# CH32V317W-R0-1v0.net
KiCad netlist of a schematic drawn in Altium Designer
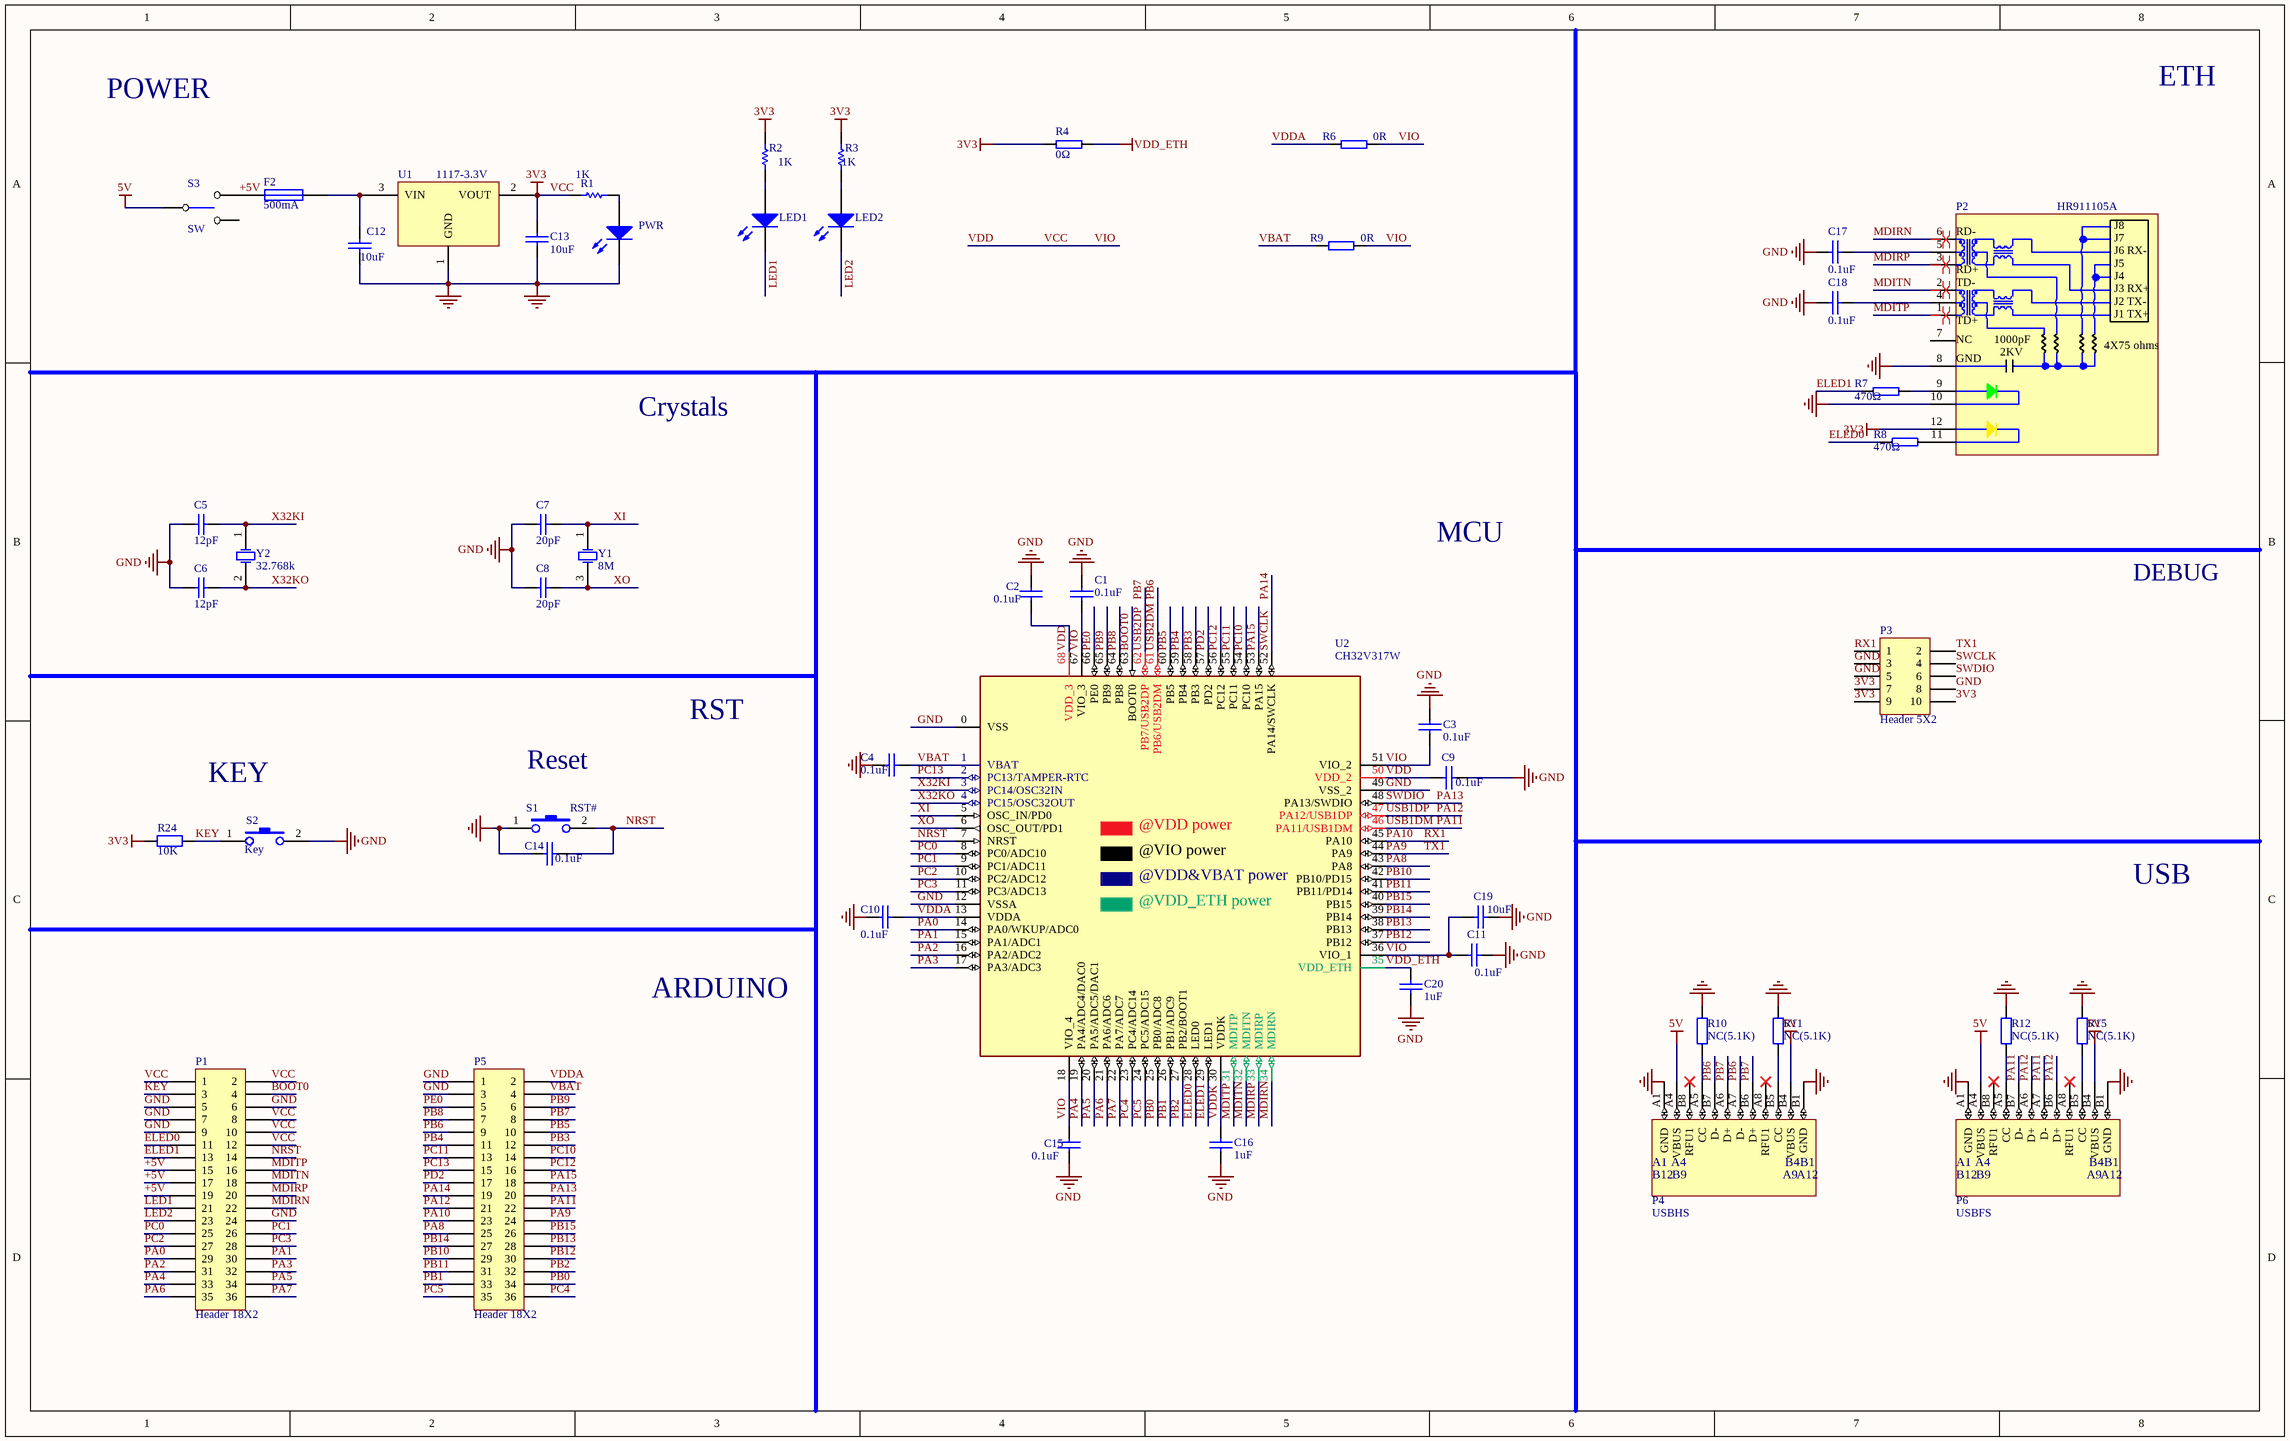
[diagram p0: CH32V317W-R0-1v0.SchDoc]

(export (version "E")
  (design (tool "Eeschema 10.0.6"))
  (components
    (comp (ref "C1")
      (value "0.1uF")
      (footprint "0603_C")
      (description "Capacitor")
      (libsource (lib "*") (part "CAP"))
    )
    (comp (ref "C2")
      (value "0.1uF")
      (footprint "0603_C")
      (description "Capacitor")
      (libsource (lib "*") (part "CAP"))
    )
    (comp (ref "C3")
      (value "0.1uF")
      (footprint "0603_C")
      (description "Capacitor")
      (libsource (lib "*") (part "CAP"))
    )
    (comp (ref "C4")
      (value "0.1uF")
      (footprint "0603_C")
      (description "Capacitor")
      (libsource (lib "*") (part "CAP"))
    )
    (comp (ref "C5")
      (value "12pF")
      (footprint "0603_C")
      (description "Capacitor")
      (libsource (lib "Miscellaneous Devices") (part "Cap"))
    )
    (comp (ref "C6")
      (value "12pF")
      (footprint "0603_C")
      (description "Capacitor")
      (libsource (lib "Miscellaneous Devices") (part "Cap"))
    )
    (comp (ref "C7")
      (value "20pF")
      (footprint "0603_C")
      (description "Capacitor")
      (libsource (lib "Miscellaneous Devices") (part "Cap"))
    )
    (comp (ref "C8")
      (value "20pF")
      (footprint "0603_C")
      (description "Capacitor")
      (libsource (lib "Miscellaneous Devices") (part "Cap"))
    )
    (comp (ref "C9")
      (value "0.1uF")
      (footprint "0603_C")
      (description "Capacitor")
      (libsource (lib "*") (part "CAP"))
    )
    (comp (ref "C10")
      (value "0.1uF")
      (footprint "0603_C")
      (description "Capacitor")
      (libsource (lib "*") (part "CAP"))
    )
    (comp (ref "C11")
      (value "0.1uF")
      (footprint "0603_C")
      (description "Capacitor")
      (libsource (lib "*") (part "CAP"))
    )
    (comp (ref "C12")
      (value "10uF")
      (footprint "0603_C")
      (description "Capacitor")
      (libsource (lib "*") (part "CAP"))
    )
    (comp (ref "C13")
      (value "10uF")
      (footprint "0603_C")
      (description "Capacitor")
      (libsource (lib "*") (part "CAP"))
    )
    (comp (ref "C14")
      (value "0.1uF")
      (footprint "0603_C")
      (description "Capacitor")
      (libsource (lib "") (part "CAP_1"))
    )
    (comp (ref "C15")
      (value "0.1uF")
      (footprint "0603_C")
      (description "Capacitor")
      (libsource (lib "*") (part "CAP"))
    )
    (comp (ref "C16")
      (value "1uF")
      (footprint "0603_C")
      (description "Capacitor")
      (libsource (lib "wch_sch_others") (part "CAP"))
    )
    (comp (ref "C17")
      (value "0.1uF")
      (footprint "0603_C")
      (description "Capacitor")
      (libsource (lib "wch_sch_others") (part "CAP"))
    )
    (comp (ref "C18")
      (value "0.1uF")
      (footprint "0603_C")
      (description "Capacitor")
      (libsource (lib "wch_sch_others") (part "CAP"))
    )
    (comp (ref "C19")
      (value "10uF")
      (footprint "0603_C")
      (description "Capacitor")
      (libsource (lib "*") (part "CAP"))
    )
    (comp (ref "C20")
      (value "1uF")
      (footprint "0603_C")
      (description "Capacitor")
      (libsource (lib "*") (part "CAP"))
    )
    (comp (ref "F2")
      (value "500mA")
      (footprint "0603")
      (description "Fuse")
      (libsource (lib "*") (part "FUSE1"))
    )
    (comp (ref "LED1")
      (value "LED1   blue")
      (footprint "0603+")
      (description "Typical INFRARED GaAs LED")
      (fields (field (name "PUBLISHER") "Altium Limited"))
      (libsource (lib "Miscellaneous Devices") (part "LED0"))
    )
    (comp (ref "LED2")
      (value "LED2  blue")
      (footprint "0603+")
      (description "Typical INFRARED GaAs LED")
      (fields (field (name "PUBLISHER") "Altium Limited"))
      (libsource (lib "Miscellaneous Devices") (part "LED0"))
    )
    (comp (ref "P1")
      (value "Header 18X2")
      (footprint "IDC36-2.54mm")
      (description "Header, 18-Pin, Dual row")
      (fields (field (name "PUBLISHER") "Altium Limited"))
      (libsource (lib "Miscellaneous Connectors") (part "Header 18X2"))
    )
    (comp (ref "P2") (value "HR911105A") (footprint "HR911105A") (libsource (lib "*") (part "HR911105A")))
    (comp (ref "P3")
      (value "Header 5X2")
      (footprint "IDC10-2.54mm")
      (description "Header, 5-Pin, Dual row")
      (fields (field (name "PUBLISHER") "Altium Limited"))
      (libsource (lib "Miscellaneous Connectors") (part "Header 5X2"))
    )
    (comp (ref "P4")
      (value "USBHS")
      (footprint "TYPE-C-Receptacle-2.0")
      (libsource (lib "*") (part "TYPE-C1"))
    )
    (comp (ref "P5")
      (value "Header 18X2")
      (footprint "IDC36-2.54mm")
      (description "Header, 18-Pin, Dual row")
      (fields (field (name "PUBLISHER") "Altium Limited"))
      (libsource (lib "Miscellaneous Connectors") (part "Header 18X2"))
    )
    (comp (ref "P6")
      (value "USBFS")
      (footprint "TYPE-C-Receptacle-2.0")
      (libsource (lib "*") (part "TYPE-C1"))
    )
    (comp (ref "PWR")
      (value "POWER  red")
      (footprint "0603+")
      (description "Typical INFRARED GaAs LED")
      (fields (field (name "PUBLISHER") "Altium Limited"))
      (libsource (lib "Miscellaneous Devices") (part "LED0"))
    )
    (comp (ref "R1")
      (value "1K")
      (footprint "0603")
      (description "Semiconductor Resistor")
      (libsource (lib "Miscellaneous Devices") (part "Res Semi"))
    )
    (comp (ref "R2")
      (value "1K")
      (footprint "0603")
      (description "Semiconductor Resistor")
      (libsource (lib "Miscellaneous Devices") (part "Res Semi"))
    )
    (comp (ref "R3")
      (value "1K")
      (footprint "0603")
      (description "Semiconductor Resistor")
      (libsource (lib "Miscellaneous Devices") (part "Res Semi"))
    )
    (comp (ref "R4") (value "0Ω") (footprint "0603") (libsource (lib "wch_sch_others") (part "RES")))
    (comp (ref "R6") (value "0R") (footprint "0603") (libsource (lib "*") (part "R")))
    (comp (ref "R7") (value "470Ω") (footprint "0603") (libsource (lib "") (part "RES_1")))
    (comp (ref "R8") (value "470Ω") (footprint "0603") (libsource (lib "") (part "RES_1")))
    (comp (ref "R9") (value "0R") (footprint "0603") (libsource (lib "*") (part "R")))
    (comp (ref "R10")
      (value "NC(5.1K)")
      (footprint "0603")
      (description "Resistor")
      (libsource (lib "Miscellaneous Devices") (part "Res2"))
    )
    (comp (ref "R11")
      (value "NC(5.1K)")
      (footprint "0603")
      (description "Resistor")
      (libsource (lib "Miscellaneous Devices") (part "Res2"))
    )
    (comp (ref "R12")
      (value "NC(5.1K)")
      (footprint "0603")
      (description "Resistor")
      (libsource (lib "Miscellaneous Devices") (part "Res2"))
    )
    (comp (ref "R15")
      (value "NC(5.1K)")
      (footprint "0603")
      (description "Resistor")
      (libsource (lib "Miscellaneous Devices") (part "Res2"))
    )
    (comp (ref "R24")
      (value "10K")
      (footprint "0603")
      (description "Resistor")
      (libsource (lib "") (part "Res2_1"))
    )
    (comp (ref "S1")
      (value "RST#")
      (footprint "SMD_6.1x3.65x2.5mm-KEY")
      (libsource (lib "wch_sch_others") (part "KEY1"))
    )
    (comp (ref "S2")
      (value "Key")
      (footprint "SMD_6.1x3.65x2.5mm-KEY")
      (libsource (lib "wch_sch_others") (part "KEY1"))
    )
    (comp (ref "S3") (value "SW") (footprint "SW1") (libsource (lib "MYSCH") (part "SW")))
    (comp (ref "U1")
      (value "1117-3.3V")
      (footprint "SOT-223")
      (libsource (lib "wch_sch_others") (part "1117-3.3V"))
    )
    (comp (ref "U2")
      (value "CH32V317W")
      (footprint "QFN68_8X8")
      (description "RISC-V FPU HD-MCU, 144MHz, USB_480M, USB OTG, 100M Ethernet & Phy, 2*CAN")
      (libsource (lib "CHXXX") (part "CH32V317W"))
    )
    (comp (ref "Y1")
      (value "8M")
      (footprint "XT3225")
      (description "Crystal Oscillator")
      (fields (field (name "PUBLISHER") "Altium Limited"))
      (libsource (lib "") (part "XTAL_1"))
    )
    (comp (ref "Y2")
      (value "32.768k")
      (footprint "FC-135")
      (description "Crystal Oscillator")
      (fields (field (name "PUBLISHER") "Altium Limited"))
      (libsource (lib "Miscellaneous Devices") (part "XTAL"))
    )
  )
  (nets
    (net (code "1") (name "/+5V") (class "Default")
      (node (ref "F2") (pin "1") (pinfunction "1_1") (pintype "passive"))
      (node (ref "P1") (pin "15") (pinfunction "15_15") (pintype "passive"))
      (node (ref "P1") (pin "17") (pinfunction "17_17") (pintype "passive"))
      (node (ref "P1") (pin "19") (pinfunction "19_19") (pintype "passive"))
      (node (ref "S3") (pin "3") (pinfunction "3_3") (pintype "passive"))
    )
    (net (code "2") (name "/BOOT0") (class "Default")
      (node (ref "P1") (pin "4") (pinfunction "4_4") (pintype "passive"))
      (node (ref "U2") (pin "63") (pinfunction "BOOT0_63") (pintype "input"))
    )
    (net (code "3") (name "/ELED0") (class "Default")
      (node (ref "P1") (pin "11") (pinfunction "11_11") (pintype "passive"))
      (node (ref "R8") (pin "1") (pintype "passive"))
      (node (ref "U2") (pin "28") (pinfunction "LED0_28") (pintype "bidirectional"))
    )
    (net (code "4") (name "/ELED1") (class "Default")
      (node (ref "P1") (pin "13") (pinfunction "13_13") (pintype "passive"))
      (node (ref "R7") (pin "1") (pintype "passive"))
      (node (ref "U2") (pin "29") (pinfunction "LED1_29") (pintype "bidirectional"))
    )
    (net (code "5") (name "/KEY") (class "Default")
      (node (ref "P1") (pin "3") (pinfunction "3_3") (pintype "passive"))
      (node (ref "R24") (pin "1") (pinfunction "1_1") (pintype "passive"))
      (node (ref "S2") (pin "1") (pinfunction "1_1") (pintype "passive"))
    )
    (net (code "6") (name "/LED1") (class "Default")
      (node (ref "LED1") (pin "2") (pinfunction "K_2") (pintype "passive"))
      (node (ref "P1") (pin "21") (pinfunction "21_21") (pintype "passive"))
    )
    (net (code "7") (name "/LED2") (class "Default")
      (node (ref "LED2") (pin "2") (pinfunction "K_2") (pintype "passive"))
      (node (ref "P1") (pin "23") (pinfunction "23_23") (pintype "passive"))
    )
    (net (code "8") (name "/MDIRN") (class "Default")
      (node (ref "P1") (pin "22") (pinfunction "22_22") (pintype "passive"))
      (node (ref "P2") (pin "6") (pintype "passive"))
      (node (ref "U2") (pin "34") (pinfunction "MDIRN_34") (pintype "bidirectional"))
    )
    (net (code "9") (name "/MDIRP") (class "Default")
      (node (ref "P1") (pin "20") (pinfunction "20_20") (pintype "passive"))
      (node (ref "P2") (pin "3") (pintype "passive"))
      (node (ref "U2") (pin "33") (pinfunction "MDIRP_33") (pintype "bidirectional"))
    )
    (net (code "10") (name "/MDITN") (class "Default")
      (node (ref "P1") (pin "18") (pinfunction "18_18") (pintype "passive"))
      (node (ref "P2") (pin "2") (pintype "passive"))
      (node (ref "U2") (pin "32") (pinfunction "MDITN_32") (pintype "bidirectional"))
    )
    (net (code "11") (name "/MDITP") (class "Default")
      (node (ref "P1") (pin "16") (pinfunction "16_16") (pintype "passive"))
      (node (ref "P2") (pin "1") (pintype "passive"))
      (node (ref "U2") (pin "31") (pinfunction "MDITP_31") (pintype "bidirectional"))
    )
    (net (code "12") (name "/NRST") (class "Default")
      (node (ref "C14") (pin "2") (pinfunction "2_2") (pintype "passive"))
      (node (ref "P1") (pin "14") (pinfunction "14_14") (pintype "passive"))
      (node (ref "S1") (pin "2") (pinfunction "2_2") (pintype "passive"))
      (node (ref "U2") (pin "7") (pinfunction "NRST_7") (pintype "input"))
    )
    (net (code "13") (name "/PA0") (class "Default")
      (node (ref "P1") (pin "29") (pinfunction "29_29") (pintype "passive"))
      (node (ref "U2") (pin "14") (pinfunction "PA0/WKUP/ADC0_14") (pintype "bidirectional"))
    )
    (net (code "14") (name "/PA1") (class "Default")
      (node (ref "P1") (pin "30") (pinfunction "30_30") (pintype "passive"))
      (node (ref "U2") (pin "15") (pinfunction "PA1/ADC1_15") (pintype "bidirectional"))
    )
    (net (code "15") (name "/PA2") (class "Default")
      (node (ref "P1") (pin "31") (pinfunction "31_31") (pintype "passive"))
      (node (ref "U2") (pin "16") (pinfunction "PA2/ADC2_16") (pintype "bidirectional"))
    )
    (net (code "16") (name "/PA3") (class "Default")
      (node (ref "P1") (pin "32") (pinfunction "32_32") (pintype "passive"))
      (node (ref "U2") (pin "17") (pinfunction "PA3/ADC3_17") (pintype "bidirectional"))
    )
    (net (code "17") (name "/PA4") (class "Default")
      (node (ref "P1") (pin "33") (pinfunction "33_33") (pintype "passive"))
      (node (ref "U2") (pin "19") (pinfunction "PA4/ADC4/DAC0_19") (pintype "bidirectional"))
    )
    (net (code "18") (name "/PA5") (class "Default")
      (node (ref "P1") (pin "34") (pinfunction "34_34") (pintype "passive"))
      (node (ref "U2") (pin "20") (pinfunction "PA5/ADC5/DAC1_20") (pintype "bidirectional"))
    )
    (net (code "19") (name "/PA6") (class "Default")
      (node (ref "P1") (pin "35") (pinfunction "35_35") (pintype "passive"))
      (node (ref "U2") (pin "21") (pinfunction "PA6/ADC6_21") (pintype "bidirectional"))
    )
    (net (code "20") (name "/PA7") (class "Default")
      (node (ref "P1") (pin "36") (pinfunction "36_36") (pintype "passive"))
      (node (ref "U2") (pin "22") (pinfunction "PA7/ADC7_22") (pintype "bidirectional"))
    )
    (net (code "21") (name "/PA8") (class "Default")
      (node (ref "P5") (pin "25") (pinfunction "25_25") (pintype "passive"))
      (node (ref "U2") (pin "43") (pinfunction "PA8_43") (pintype "bidirectional"))
    )
    (net (code "22") (name "/PA9") (class "Default")
      (node (ref "P3") (pin "2") (pinfunction "2_2") (pintype "passive"))
      (node (ref "P5") (pin "24") (pinfunction "24_24") (pintype "passive"))
      (node (ref "U2") (pin "44") (pinfunction "PA9_44") (pintype "bidirectional"))
    )
    (net (code "23") (name "/PA10") (class "Default")
      (node (ref "P3") (pin "1") (pinfunction "1_1") (pintype "passive"))
      (node (ref "P5") (pin "23") (pinfunction "23_23") (pintype "passive"))
      (node (ref "U2") (pin "45") (pinfunction "PA10_45") (pintype "bidirectional"))
    )
    (net (code "24") (name "/PA11") (class "Default")
      (node (ref "P5") (pin "22") (pinfunction "22_22") (pintype "passive"))
      (node (ref "P6") (pin "A7") (pinfunction "D-_A7") (pintype "bidirectional"))
      (node (ref "P6") (pin "B7") (pinfunction "D-_B7") (pintype "bidirectional"))
      (node (ref "U2") (pin "46") (pinfunction "PA11/USB1DM_46") (pintype "bidirectional"))
    )
    (net (code "25") (name "/PA12") (class "Default")
      (node (ref "P5") (pin "21") (pinfunction "21_21") (pintype "passive"))
      (node (ref "P6") (pin "A6") (pinfunction "D+_A6") (pintype "bidirectional"))
      (node (ref "P6") (pin "B6") (pinfunction "D+_B6") (pintype "bidirectional"))
      (node (ref "U2") (pin "47") (pinfunction "PA12/USB1DP_47") (pintype "bidirectional"))
    )
    (net (code "26") (name "/PA13") (class "Default")
      (node (ref "P3") (pin "6") (pinfunction "6_6") (pintype "passive"))
      (node (ref "P5") (pin "20") (pinfunction "20_20") (pintype "passive"))
      (node (ref "U2") (pin "48") (pinfunction "PA13/SWDIO_48") (pintype "bidirectional"))
    )
    (net (code "27") (name "/PA14") (class "Default")
      (node (ref "P3") (pin "4") (pinfunction "4_4") (pintype "passive"))
      (node (ref "P5") (pin "19") (pinfunction "19_19") (pintype "passive"))
      (node (ref "U2") (pin "52") (pinfunction "PA14/SWCLK_52") (pintype "bidirectional"))
    )
    (net (code "28") (name "/PA15") (class "Default")
      (node (ref "P5") (pin "18") (pinfunction "18_18") (pintype "passive"))
      (node (ref "U2") (pin "53") (pinfunction "PA15_53") (pintype "bidirectional"))
    )
    (net (code "29") (name "/PB0") (class "Default")
      (node (ref "P5") (pin "34") (pinfunction "34_34") (pintype "passive"))
      (node (ref "U2") (pin "25") (pinfunction "PB0/ADC8_25") (pintype "bidirectional"))
    )
    (net (code "30") (name "/PB1") (class "Default")
      (node (ref "P5") (pin "33") (pinfunction "33_33") (pintype "passive"))
      (node (ref "U2") (pin "26") (pinfunction "PB1/ADC9_26") (pintype "bidirectional"))
    )
    (net (code "31") (name "/PB2") (class "Default")
      (node (ref "P5") (pin "32") (pinfunction "32_32") (pintype "passive"))
      (node (ref "U2") (pin "27") (pinfunction "PB2/BOOT1_27") (pintype "bidirectional"))
    )
    (net (code "32") (name "/PB3") (class "Default")
      (node (ref "P5") (pin "12") (pinfunction "12_12") (pintype "passive"))
      (node (ref "U2") (pin "58") (pinfunction "PB3_58") (pintype "bidirectional"))
    )
    (net (code "33") (name "/PB4") (class "Default")
      (node (ref "P5") (pin "11") (pinfunction "11_11") (pintype "passive"))
      (node (ref "U2") (pin "59") (pinfunction "PB4_59") (pintype "bidirectional"))
    )
    (net (code "34") (name "/PB5") (class "Default")
      (node (ref "P5") (pin "10") (pinfunction "10_10") (pintype "passive"))
      (node (ref "U2") (pin "60") (pinfunction "PB5_60") (pintype "bidirectional"))
    )
    (net (code "35") (name "/PB6") (class "Default")
      (node (ref "P4") (pin "A7") (pinfunction "D-_A7") (pintype "bidirectional"))
      (node (ref "P4") (pin "B7") (pinfunction "D-_B7") (pintype "bidirectional"))
      (node (ref "P5") (pin "9") (pinfunction "9_9") (pintype "passive"))
      (node (ref "U2") (pin "61") (pinfunction "PB6/USB2DM_61") (pintype "bidirectional"))
    )
    (net (code "36") (name "/PB7") (class "Default")
      (node (ref "P4") (pin "A6") (pinfunction "D+_A6") (pintype "bidirectional"))
      (node (ref "P4") (pin "B6") (pinfunction "D+_B6") (pintype "bidirectional"))
      (node (ref "P5") (pin "8") (pinfunction "8_8") (pintype "passive"))
      (node (ref "U2") (pin "62") (pinfunction "PB7/USB2DP_62") (pintype "bidirectional"))
    )
    (net (code "37") (name "/PB8") (class "Default")
      (node (ref "P5") (pin "7") (pinfunction "7_7") (pintype "passive"))
      (node (ref "U2") (pin "64") (pinfunction "PB8_64") (pintype "bidirectional"))
    )
    (net (code "38") (name "/PB9") (class "Default")
      (node (ref "P5") (pin "6") (pinfunction "6_6") (pintype "passive"))
      (node (ref "U2") (pin "65") (pinfunction "PB9_65") (pintype "bidirectional"))
    )
    (net (code "39") (name "/PB10") (class "Default")
      (node (ref "P5") (pin "29") (pinfunction "29_29") (pintype "passive"))
      (node (ref "U2") (pin "42") (pinfunction "PB10/PD15_42") (pintype "bidirectional"))
    )
    (net (code "40") (name "/PB11") (class "Default")
      (node (ref "P5") (pin "31") (pinfunction "31_31") (pintype "passive"))
      (node (ref "U2") (pin "41") (pinfunction "PB11/PD14_41") (pintype "bidirectional"))
    )
    (net (code "41") (name "/PB12") (class "Default")
      (node (ref "P5") (pin "30") (pinfunction "30_30") (pintype "passive"))
      (node (ref "U2") (pin "37") (pinfunction "PB12_37") (pintype "bidirectional"))
    )
    (net (code "42") (name "/PB13") (class "Default")
      (node (ref "P5") (pin "28") (pinfunction "28_28") (pintype "passive"))
      (node (ref "U2") (pin "38") (pinfunction "PB13_38") (pintype "bidirectional"))
    )
    (net (code "43") (name "/PB14") (class "Default")
      (node (ref "P5") (pin "27") (pinfunction "27_27") (pintype "passive"))
      (node (ref "U2") (pin "39") (pinfunction "PB14_39") (pintype "bidirectional"))
    )
    (net (code "44") (name "/PB15") (class "Default")
      (node (ref "P5") (pin "26") (pinfunction "26_26") (pintype "passive"))
      (node (ref "U2") (pin "40") (pinfunction "PB15_40") (pintype "bidirectional"))
    )
    (net (code "45") (name "/PC0") (class "Default")
      (node (ref "P1") (pin "25") (pinfunction "25_25") (pintype "passive"))
      (node (ref "U2") (pin "8") (pinfunction "PC0/ADC10_8") (pintype "bidirectional"))
    )
    (net (code "46") (name "/PC1") (class "Default")
      (node (ref "P1") (pin "26") (pinfunction "26_26") (pintype "passive"))
      (node (ref "U2") (pin "9") (pinfunction "PC1/ADC11_9") (pintype "bidirectional"))
    )
    (net (code "47") (name "/PC2") (class "Default")
      (node (ref "P1") (pin "27") (pinfunction "27_27") (pintype "passive"))
      (node (ref "U2") (pin "10") (pinfunction "PC2/ADC12_10") (pintype "bidirectional"))
    )
    (net (code "48") (name "/PC3") (class "Default")
      (node (ref "P1") (pin "28") (pinfunction "28_28") (pintype "passive"))
      (node (ref "U2") (pin "11") (pinfunction "PC3/ADC13_11") (pintype "bidirectional"))
    )
    (net (code "49") (name "/PC4") (class "Default")
      (node (ref "P5") (pin "36") (pinfunction "36_36") (pintype "passive"))
      (node (ref "U2") (pin "23") (pinfunction "PC4/ADC14_23") (pintype "bidirectional"))
    )
    (net (code "50") (name "/PC5") (class "Default")
      (node (ref "P5") (pin "35") (pinfunction "35_35") (pintype "passive"))
      (node (ref "U2") (pin "24") (pinfunction "PC5/ADC15_24") (pintype "bidirectional"))
    )
    (net (code "51") (name "/PC10") (class "Default")
      (node (ref "P5") (pin "14") (pinfunction "14_14") (pintype "passive"))
      (node (ref "U2") (pin "54") (pinfunction "PC10_54") (pintype "bidirectional"))
    )
    (net (code "52") (name "/PC11") (class "Default")
      (node (ref "P5") (pin "13") (pinfunction "13_13") (pintype "passive"))
      (node (ref "U2") (pin "55") (pinfunction "PC11_55") (pintype "bidirectional"))
    )
    (net (code "53") (name "/PC12") (class "Default")
      (node (ref "P5") (pin "16") (pinfunction "16_16") (pintype "passive"))
      (node (ref "U2") (pin "56") (pinfunction "PC12_56") (pintype "bidirectional"))
    )
    (net (code "54") (name "/PC13") (class "Default")
      (node (ref "P5") (pin "15") (pinfunction "15_15") (pintype "passive"))
      (node (ref "U2") (pin "2") (pinfunction "PC13/TAMPER-RTC_2") (pintype "bidirectional"))
    )
    (net (code "55") (name "/PD2") (class "Default")
      (node (ref "P5") (pin "17") (pinfunction "17_17") (pintype "passive"))
      (node (ref "U2") (pin "57") (pinfunction "PD2_57") (pintype "bidirectional"))
    )
    (net (code "56") (name "/PE0") (class "Default")
      (node (ref "P5") (pin "5") (pinfunction "5_5") (pintype "passive"))
      (node (ref "U2") (pin "66") (pinfunction "PE0_66") (pintype "bidirectional"))
    )
    (net (code "57") (name "/VBAT") (class "Default")
      (node (ref "C4") (pin "2") (pinfunction "2_2") (pintype "passive"))
      (node (ref "P5") (pin "4") (pinfunction "4_4") (pintype "passive"))
      (node (ref "R9") (pin "2") (pinfunction "2_2") (pintype "passive"))
      (node (ref "U2") (pin "1") (pinfunction "VBAT_1") (pintype "power_in"))
    )
    (net (code "58") (name "/VDDA") (class "Default")
      (node (ref "C10") (pin "1") (pinfunction "1_1") (pintype "passive"))
      (node (ref "P5") (pin "2") (pinfunction "2_2") (pintype "passive"))
      (node (ref "R6") (pin "2") (pinfunction "2_2") (pintype "passive"))
      (node (ref "U2") (pin "13") (pinfunction "VDDA_13") (pintype "power_in"))
    )
    (net (code "59") (name "/VDDK") (class "Default")
      (node (ref "C16") (pin "2") (pinfunction "2_2") (pintype "passive"))
      (node (ref "U2") (pin "30") (pinfunction "VDDK_30") (pintype "power_in"))
    )
    (net (code "60") (name "/X32KI") (class "Default")
      (node (ref "C5") (pin "1") (pinfunction "1_1") (pintype "passive"))
      (node (ref "U2") (pin "3") (pinfunction "PC14/OSC32IN_3") (pintype "bidirectional"))
      (node (ref "Y2") (pin "1") (pinfunction "OSC1_1") (pintype "passive"))
    )
    (net (code "61") (name "/X32KO") (class "Default")
      (node (ref "C6") (pin "1") (pinfunction "1_1") (pintype "passive"))
      (node (ref "U2") (pin "4") (pinfunction "PC15/OSC32OUT_4") (pintype "bidirectional"))
      (node (ref "Y2") (pin "2") (pinfunction "OSC2_2") (pintype "passive"))
    )
    (net (code "62") (name "/XI") (class "Default")
      (node (ref "C7") (pin "2") (pinfunction "2_2") (pintype "passive"))
      (node (ref "U2") (pin "5") (pinfunction "OSC_IN/PD0_5") (pintype "input"))
      (node (ref "Y1") (pin "1") (pinfunction "OSC1_1") (pintype "passive"))
    )
    (net (code "63") (name "/XO") (class "Default")
      (node (ref "C8") (pin "2") (pinfunction "2_2") (pintype "passive"))
      (node (ref "U2") (pin "6") (pinfunction "OSC_OUT/PD1_6") (pintype "output"))
      (node (ref "Y1") (pin "3") (pinfunction "OSC2_3") (pintype "passive"))
    )
    (net (code "64") (name "3V3") (class "Default")
      (node (ref "C1") (pin "2") (pinfunction "2_2") (pintype "passive"))
      (node (ref "C11") (pin "2") (pinfunction "2_2") (pintype "passive"))
      (node (ref "C13") (pin "1") (pinfunction "1_1") (pintype "passive"))
      (node (ref "C15") (pin "2") (pinfunction "2_2") (pintype "passive"))
      (node (ref "C19") (pin "2") (pinfunction "2_2") (pintype "passive"))
      (node (ref "C2") (pin "2") (pinfunction "2_2") (pintype "passive"))
      (node (ref "C3") (pin "2") (pinfunction "2_2") (pintype "passive"))
      (node (ref "C9") (pin "2") (pinfunction "2_2") (pintype "passive"))
      (node (ref "P1") (pin "1") (pinfunction "1_1") (pintype "passive"))
      (node (ref "P1") (pin "10") (pinfunction "10_10") (pintype "passive"))
      (node (ref "P1") (pin "12") (pinfunction "12_12") (pintype "passive"))
      (node (ref "P1") (pin "2") (pinfunction "2_2") (pintype "passive"))
      (node (ref "P1") (pin "8") (pinfunction "8_8") (pintype "passive"))
      (node (ref "P2") (pin "12") (pintype "passive"))
      (node (ref "P3") (pin "10") (pinfunction "10_10") (pintype "passive"))
      (node (ref "P3") (pin "7") (pinfunction "7_7") (pintype "passive"))
      (node (ref "P3") (pin "9") (pinfunction "9_9") (pintype "passive"))
      (node (ref "R1") (pin "2") (pinfunction "2_2") (pintype "passive"))
      (node (ref "R2") (pin "1") (pinfunction "1_1") (pintype "passive"))
      (node (ref "R24") (pin "2") (pinfunction "2_2") (pintype "passive"))
      (node (ref "R3") (pin "1") (pinfunction "1_1") (pintype "passive"))
      (node (ref "R4") (pin "2") (pintype "passive"))
      (node (ref "R6") (pin "1") (pinfunction "1_1") (pintype "passive"))
      (node (ref "R9") (pin "1") (pinfunction "1_1") (pintype "passive"))
      (node (ref "U1") (pin "2") (pinfunction "VOUT_2") (pintype "passive"))
      (node (ref "U2") (pin "18") (pinfunction "VIO_4_18") (pintype "power_in"))
      (node (ref "U2") (pin "36") (pinfunction "VIO_1_36") (pintype "power_in"))
      (node (ref "U2") (pin "50") (pinfunction "VDD_2_50") (pintype "power_in"))
      (node (ref "U2") (pin "51") (pinfunction "VIO_2_51") (pintype "power_in"))
      (node (ref "U2") (pin "67") (pinfunction "VIO_3_67") (pintype "power_in"))
      (node (ref "U2") (pin "68") (pinfunction "VDD_3_68") (pintype "power_in"))
    )
    (net (code "65") (name "5V") (class "Default")
      (node (ref "P4") (pin "A4") (pinfunction "VBUS_A4") (pintype "bidirectional"))
      (node (ref "P4") (pin "B4") (pinfunction "VBUS_B4") (pintype "bidirectional"))
      (node (ref "P6") (pin "A4") (pinfunction "VBUS_A4") (pintype "bidirectional"))
      (node (ref "P6") (pin "B4") (pinfunction "VBUS_B4") (pintype "bidirectional"))
      (node (ref "S3") (pin "1") (pinfunction "1_1") (pintype "passive"))
    )
    (net (code "66") (name "GND") (class "Default")
      (node (ref "C1") (pin "1") (pinfunction "1_1") (pintype "passive"))
      (node (ref "C10") (pin "2") (pinfunction "2_2") (pintype "passive"))
      (node (ref "C11") (pin "1") (pinfunction "1_1") (pintype "passive"))
      (node (ref "C12") (pin "2") (pinfunction "2_2") (pintype "passive"))
      (node (ref "C13") (pin "2") (pinfunction "2_2") (pintype "passive"))
      (node (ref "C14") (pin "1") (pinfunction "1_1") (pintype "passive"))
      (node (ref "C15") (pin "1") (pinfunction "1_1") (pintype "passive"))
      (node (ref "C16") (pin "1") (pinfunction "1_1") (pintype "passive"))
      (node (ref "C17") (pin "1") (pinfunction "1_1") (pintype "passive"))
      (node (ref "C18") (pin "1") (pinfunction "1_1") (pintype "passive"))
      (node (ref "C19") (pin "1") (pinfunction "1_1") (pintype "passive"))
      (node (ref "C2") (pin "1") (pinfunction "1_1") (pintype "passive"))
      (node (ref "C20") (pin "1") (pinfunction "1_1") (pintype "passive"))
      (node (ref "C3") (pin "1") (pinfunction "1_1") (pintype "passive"))
      (node (ref "C4") (pin "1") (pinfunction "1_1") (pintype "passive"))
      (node (ref "C5") (pin "2") (pinfunction "2_2") (pintype "passive"))
      (node (ref "C6") (pin "2") (pinfunction "2_2") (pintype "passive"))
      (node (ref "C7") (pin "1") (pinfunction "1_1") (pintype "passive"))
      (node (ref "C8") (pin "1") (pinfunction "1_1") (pintype "passive"))
      (node (ref "C9") (pin "1") (pinfunction "1_1") (pintype "passive"))
      (node (ref "P1") (pin "24") (pinfunction "24_24") (pintype "passive"))
      (node (ref "P1") (pin "5") (pinfunction "5_5") (pintype "passive"))
      (node (ref "P1") (pin "6") (pinfunction "6_6") (pintype "passive"))
      (node (ref "P1") (pin "7") (pinfunction "7_7") (pintype "passive"))
      (node (ref "P1") (pin "9") (pinfunction "9_9") (pintype "passive"))
      (node (ref "P2") (pin "10") (pintype "passive"))
      (node (ref "P2") (pin "8") (pintype "passive"))
      (node (ref "P3") (pin "3") (pinfunction "3_3") (pintype "passive"))
      (node (ref "P3") (pin "5") (pinfunction "5_5") (pintype "passive"))
      (node (ref "P3") (pin "8") (pinfunction "8_8") (pintype "passive"))
      (node (ref "P4") (pin "A1") (pinfunction "GND_A1") (pintype "bidirectional"))
      (node (ref "P4") (pin "B1") (pinfunction "GND_B1") (pintype "bidirectional"))
      (node (ref "P5") (pin "1") (pinfunction "1_1") (pintype "passive"))
      (node (ref "P5") (pin "3") (pinfunction "3_3") (pintype "passive"))
      (node (ref "P6") (pin "A1") (pinfunction "GND_A1") (pintype "bidirectional"))
      (node (ref "P6") (pin "B1") (pinfunction "GND_B1") (pintype "bidirectional"))
      (node (ref "PWR") (pin "2") (pinfunction "K_2") (pintype "passive"))
      (node (ref "R10") (pin "1") (pinfunction "1_1") (pintype "passive"))
      (node (ref "R11") (pin "1") (pinfunction "1_1") (pintype "passive"))
      (node (ref "R12") (pin "1") (pinfunction "1_1") (pintype "passive"))
      (node (ref "R15") (pin "1") (pinfunction "1_1") (pintype "passive"))
      (node (ref "S1") (pin "1") (pinfunction "1_1") (pintype "passive"))
      (node (ref "S2") (pin "2") (pinfunction "2_2") (pintype "passive"))
      (node (ref "U1") (pin "1") (pinfunction "GND_1") (pintype "passive"))
      (node (ref "U2") (pin "0") (pinfunction "VSS_0") (pintype "power_in"))
      (node (ref "U2") (pin "12") (pinfunction "VSSA_12") (pintype "power_in"))
      (node (ref "U2") (pin "49") (pinfunction "VSS_2_49") (pintype "power_in"))
    )
    (net (code "67") (name "Net-(C17-Pad2)") (class "Default")
      (node (ref "C17") (pin "2") (pinfunction "2_2") (pintype "passive"))
      (node (ref "P2") (pin "5") (pintype "passive"))
    )
    (net (code "68") (name "Net-(C18-Pad2)") (class "Default")
      (node (ref "C18") (pin "2") (pinfunction "2_2") (pintype "passive"))
      (node (ref "P2") (pin "4") (pintype "passive"))
    )
    (net (code "69") (name "Net-(LED1-A)") (class "Default")
      (node (ref "LED1") (pin "1") (pinfunction "A_1") (pintype "passive"))
      (node (ref "R2") (pin "2") (pinfunction "2_2") (pintype "passive"))
    )
    (net (code "70") (name "Net-(LED2-A)") (class "Default")
      (node (ref "LED2") (pin "1") (pinfunction "A_1") (pintype "passive"))
      (node (ref "R3") (pin "2") (pinfunction "2_2") (pintype "passive"))
    )
    (net (code "71") (name "Net-(P2-Pad9)") (class "Default")
      (node (ref "P2") (pin "9") (pintype "passive"))
      (node (ref "R7") (pin "2") (pintype "passive"))
    )
    (net (code "72") (name "Net-(P2-Pad11)") (class "Default")
      (node (ref "P2") (pin "11") (pintype "passive"))
      (node (ref "R8") (pin "2") (pintype "passive"))
    )
    (net (code "73") (name "Net-(P4-CC-PadA5)") (class "Default")
      (node (ref "P4") (pin "A5") (pinfunction "CC_A5") (pintype "bidirectional"))
      (node (ref "R10") (pin "2") (pinfunction "2_2") (pintype "passive"))
    )
    (net (code "74") (name "Net-(P4-CC-PadB5)") (class "Default")
      (node (ref "P4") (pin "B5") (pinfunction "CC_B5") (pintype "bidirectional"))
      (node (ref "R11") (pin "2") (pinfunction "2_2") (pintype "passive"))
    )
    (net (code "75") (name "Net-(P6-CC-PadA5)") (class "Default")
      (node (ref "P6") (pin "A5") (pinfunction "CC_A5") (pintype "bidirectional"))
      (node (ref "R12") (pin "2") (pinfunction "2_2") (pintype "passive"))
    )
    (net (code "76") (name "Net-(P6-CC-PadB5)") (class "Default")
      (node (ref "P6") (pin "B5") (pinfunction "CC_B5") (pintype "bidirectional"))
      (node (ref "R15") (pin "2") (pinfunction "2_2") (pintype "passive"))
    )
    (net (code "77") (name "Net-(PWR-A)") (class "Default")
      (node (ref "PWR") (pin "1") (pinfunction "A_1") (pintype "passive"))
      (node (ref "R1") (pin "1") (pinfunction "1_1") (pintype "passive"))
    )
    (net (code "78") (name "Net-(U1-VIN)") (class "Default")
      (node (ref "C12") (pin "1") (pinfunction "1_1") (pintype "passive"))
      (node (ref "F2") (pin "2") (pinfunction "2_2") (pintype "passive"))
      (node (ref "U1") (pin "3") (pinfunction "VIN_3") (pintype "passive"))
    )
    (net (code "79") (name "VDD_ETH") (class "Default")
      (node (ref "C20") (pin "2") (pinfunction "2_2") (pintype "passive"))
      (node (ref "R4") (pin "1") (pintype "passive"))
      (node (ref "U2") (pin "35") (pinfunction "VDD_ETH_35") (pintype "power_in"))
    )
    (net (code "80") (name "unconnected-(P2-Pad7)") (class "Default")
      (node (ref "P2") (pin "7") (pintype "passive"))
    )
    (net (code "81") (name "unconnected-(P4-RFU1-PadA8)") (class "Default")
      (node (ref "P4") (pin "A8") (pinfunction "RFU1_A8") (pintype "bidirectional+no_connect"))
    )
    (net (code "82") (name "unconnected-(P4-RFU1-PadB8)") (class "Default")
      (node (ref "P4") (pin "B8") (pinfunction "RFU1_B8") (pintype "bidirectional+no_connect"))
    )
    (net (code "83") (name "unconnected-(P6-RFU1-PadA8)") (class "Default")
      (node (ref "P6") (pin "A8") (pinfunction "RFU1_A8") (pintype "bidirectional+no_connect"))
    )
    (net (code "84") (name "unconnected-(P6-RFU1-PadB8)") (class "Default")
      (node (ref "P6") (pin "B8") (pinfunction "RFU1_B8") (pintype "bidirectional+no_connect"))
    )
    (net (code "85") (name "unconnected-(S3-Pad2)") (class "Default")
      (node (ref "S3") (pin "2") (pinfunction "2_2") (pintype "passive"))
    )
  )
)
